# 03_-_SCHEMATIC.net
KiCad netlist of a schematic drawn in Altium Designer
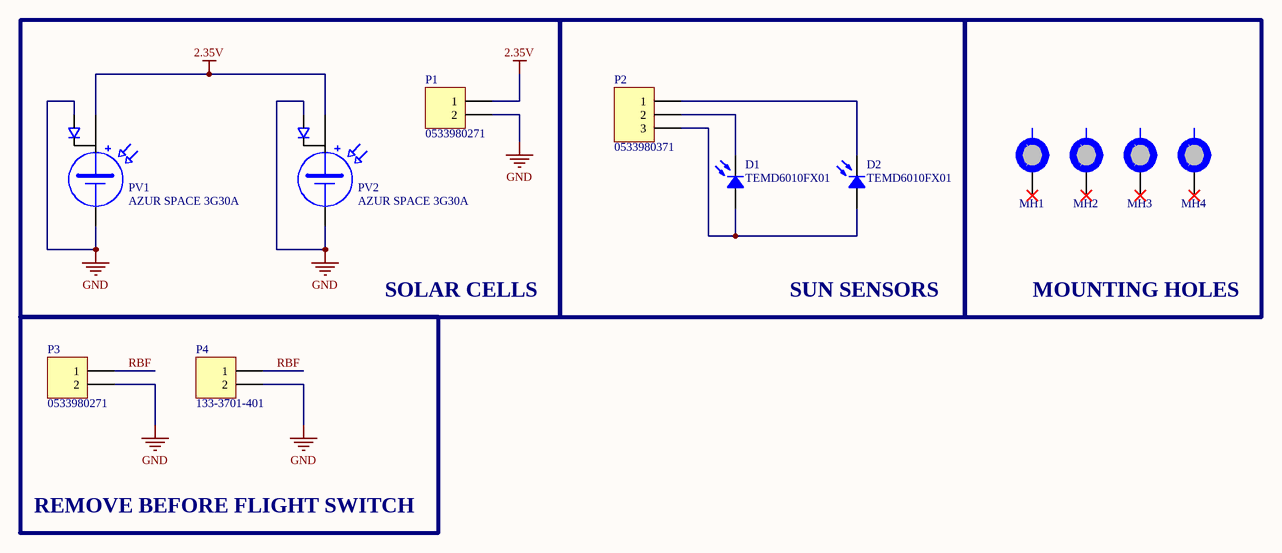
[diagram p0: [03] - SCHEMATIC.SchDoc]

(export (version "E")
  (design (tool "Eeschema 10.0.6"))
  (components
    (comp (ref "D1")
      (value "TEMD6010FX01")
      (footprint "TEMD6010FX01")
      (description "Ambient Light Sensor")
      (fields (field (name "MANUFACTURER") "Vishay Semiconductors"))
      (libsource (lib "UVG") (part "TEMD6010FX01"))
    )
    (comp (ref "D2")
      (value "TEMD6010FX01")
      (footprint "TEMD6010FX01")
      (description "Ambient Light Sensor")
      (fields (field (name "MANUFACTURER") "Vishay Semiconductors"))
      (libsource (lib "UVG") (part "TEMD6010FX01"))
    )
    (comp (ref "MH1")
      (value "MH_3.8MMNC_2.5MMD")
      (footprint "MH_3.8MMNC_2MMD_NON_COPPER_NPTH")
      (description "Mounting Hole 3.8mm Diameter (Non Copper), 2.5mm Drill NPTH")
      (libsource (lib "UVG") (part "MH_3.8MMNC_2MMD"))
    )
    (comp (ref "MH2")
      (value "MH_3.8MMNC_2.5MMD")
      (footprint "MH_3.8MMNC_2MMD_NON_COPPER_NPTH")
      (description "Mounting Hole 3.8mm Diameter (Non Copper), 2.5mm Drill NPTH")
      (libsource (lib "UVG") (part "MH_3.8MMNC_2MMD"))
    )
    (comp (ref "MH3")
      (value "MH_3.8MMNC_2.5MMD")
      (footprint "MH_3.8MMNC_2MMD_NON_COPPER_NPTH")
      (description "Mounting Hole 3.8mm Diameter (Non Copper), 2.5mm Drill NPTH")
      (libsource (lib "UVG") (part "MH_3.8MMNC_2MMD"))
    )
    (comp (ref "MH4")
      (value "MH_3.8MMNC_2.5MMD")
      (footprint "MH_3.8MMNC_2MMD_NON_COPPER_NPTH")
      (description "Mounting Hole 3.8mm Diameter (Non Copper), 2.5mm Drill NPTH")
      (libsource (lib "UVG") (part "MH_3.8MMNC_2MMD"))
    )
    (comp (ref "P1")
      (value "0533980271")
      (footprint "0533980271")
      (description "2 Positions Header, Shrouded Connector 0.049\" (1.25mm) Surface Mount, Right Angle Tin")
      (fields (field (name "MANUFACTURER") "Molex"))
      (libsource (lib "UVG") (part "0533980271"))
    )
    (comp (ref "P2")
      (value "0533980371")
      (footprint "0533980371")
      (description "3 Positions Header, Shrouded Connector 0.049\" (1.25mm) Surface Mount Tin")
      (fields (field (name "MANUFACTURER") "Molex"))
      (libsource (lib "UVG") (part "0533980371"))
    )
    (comp (ref "P3")
      (value "0533980271")
      (footprint "0533980271")
      (description "2 Positions Header, Shrouded Connector 0.049\" (1.25mm) Surface Mount, Right Angle Tin")
      (fields (field (name "MANUFACTURER") "Molex"))
      (libsource (lib "UVG") (part "0533980271"))
    )
    (comp (ref "P4")
      (value "133-3701-401")
      (footprint "133-3701-401")
      (description "MCX Connector Jack, Female Socket 50 Ohm Panel Mount Solder Cup")
      (fields (field (name "MANUFACTURER") "Bel Cinch"))
      (libsource (lib "UVG") (part "133-3701-401"))
    )
    (comp (ref "PV1")
      (value "AZUR SPACE 3G30A")
      (footprint "AZUR SPACE 3G30A")
      (description "30% Triple Junction GaAs Solar Cell Assembly")
      (libsource (lib "UVG") (part "AZUR SPACE 3G30A"))
    )
    (comp (ref "PV2")
      (value "AZUR SPACE 3G30A")
      (footprint "AZUR SPACE 3G30A")
      (description "30% Triple Junction GaAs Solar Cell Assembly")
      (libsource (lib "UVG") (part "AZUR SPACE 3G30A"))
    )
  )
  (nets
    (net (code "1") (name "/RBF") (class "Default")
      (node (ref "P3") (pin "1") (pinfunction "1_1") (pintype "passive"))
      (node (ref "P4") (pin "1") (pinfunction "1_1") (pintype "passive"))
    )
    (net (code "2") (name "2.35V") (class "Default")
      (node (ref "P1") (pin "1") (pinfunction "1_1") (pintype "passive"))
      (node (ref "PV1") (pin "1") (pinfunction "1_1") (pintype "passive"))
      (node (ref "PV2") (pin "1") (pinfunction "1_1") (pintype "passive"))
    )
    (net (code "3") (name "GND") (class "Default")
      (node (ref "P1") (pin "2") (pinfunction "2_2") (pintype "passive"))
      (node (ref "P3") (pin "2") (pinfunction "2_2") (pintype "passive"))
      (node (ref "P4") (pin "2") (pinfunction "2_2") (pintype "passive"))
      (node (ref "PV1") (pin "2") (pinfunction "2_2") (pintype "passive"))
      (node (ref "PV1") (pin "3") (pinfunction "3_3") (pintype "passive"))
      (node (ref "PV2") (pin "2") (pinfunction "2_2") (pintype "passive"))
      (node (ref "PV2") (pin "3") (pinfunction "3_3") (pintype "passive"))
    )
    (net (code "4") (name "Net-(D1-Pad1)") (class "Default")
      (node (ref "D1") (pin "1") (pinfunction "1_1") (pintype "passive"))
      (node (ref "D2") (pin "1") (pinfunction "1_1") (pintype "passive"))
      (node (ref "P2") (pin "3") (pinfunction "3_3") (pintype "passive"))
    )
    (net (code "5") (name "Net-(D1-Pad2)") (class "Default")
      (node (ref "D1") (pin "2") (pinfunction "2_2") (pintype "passive"))
      (node (ref "P2") (pin "2") (pinfunction "2_2") (pintype "passive"))
    )
    (net (code "6") (name "Net-(D2-Pad2)") (class "Default")
      (node (ref "D2") (pin "2") (pinfunction "2_2") (pintype "passive"))
      (node (ref "P2") (pin "1") (pinfunction "1_1") (pintype "passive"))
    )
    (net (code "7") (name "unconnected-(MH1-Pad1)") (class "Default")
      (node (ref "MH1") (pin "1") (pinfunction "1_1") (pintype "passive"))
    )
    (net (code "8") (name "unconnected-(MH2-Pad1)") (class "Default")
      (node (ref "MH2") (pin "1") (pinfunction "1_1") (pintype "passive"))
    )
    (net (code "9") (name "unconnected-(MH3-Pad1)") (class "Default")
      (node (ref "MH3") (pin "1") (pinfunction "1_1") (pintype "passive"))
    )
    (net (code "10") (name "unconnected-(MH4-Pad1)") (class "Default")
      (node (ref "MH4") (pin "1") (pinfunction "1_1") (pintype "passive"))
    )
  )
)
